# remote_0_1.net
KiCad netlist of a schematic drawn in EAGLE
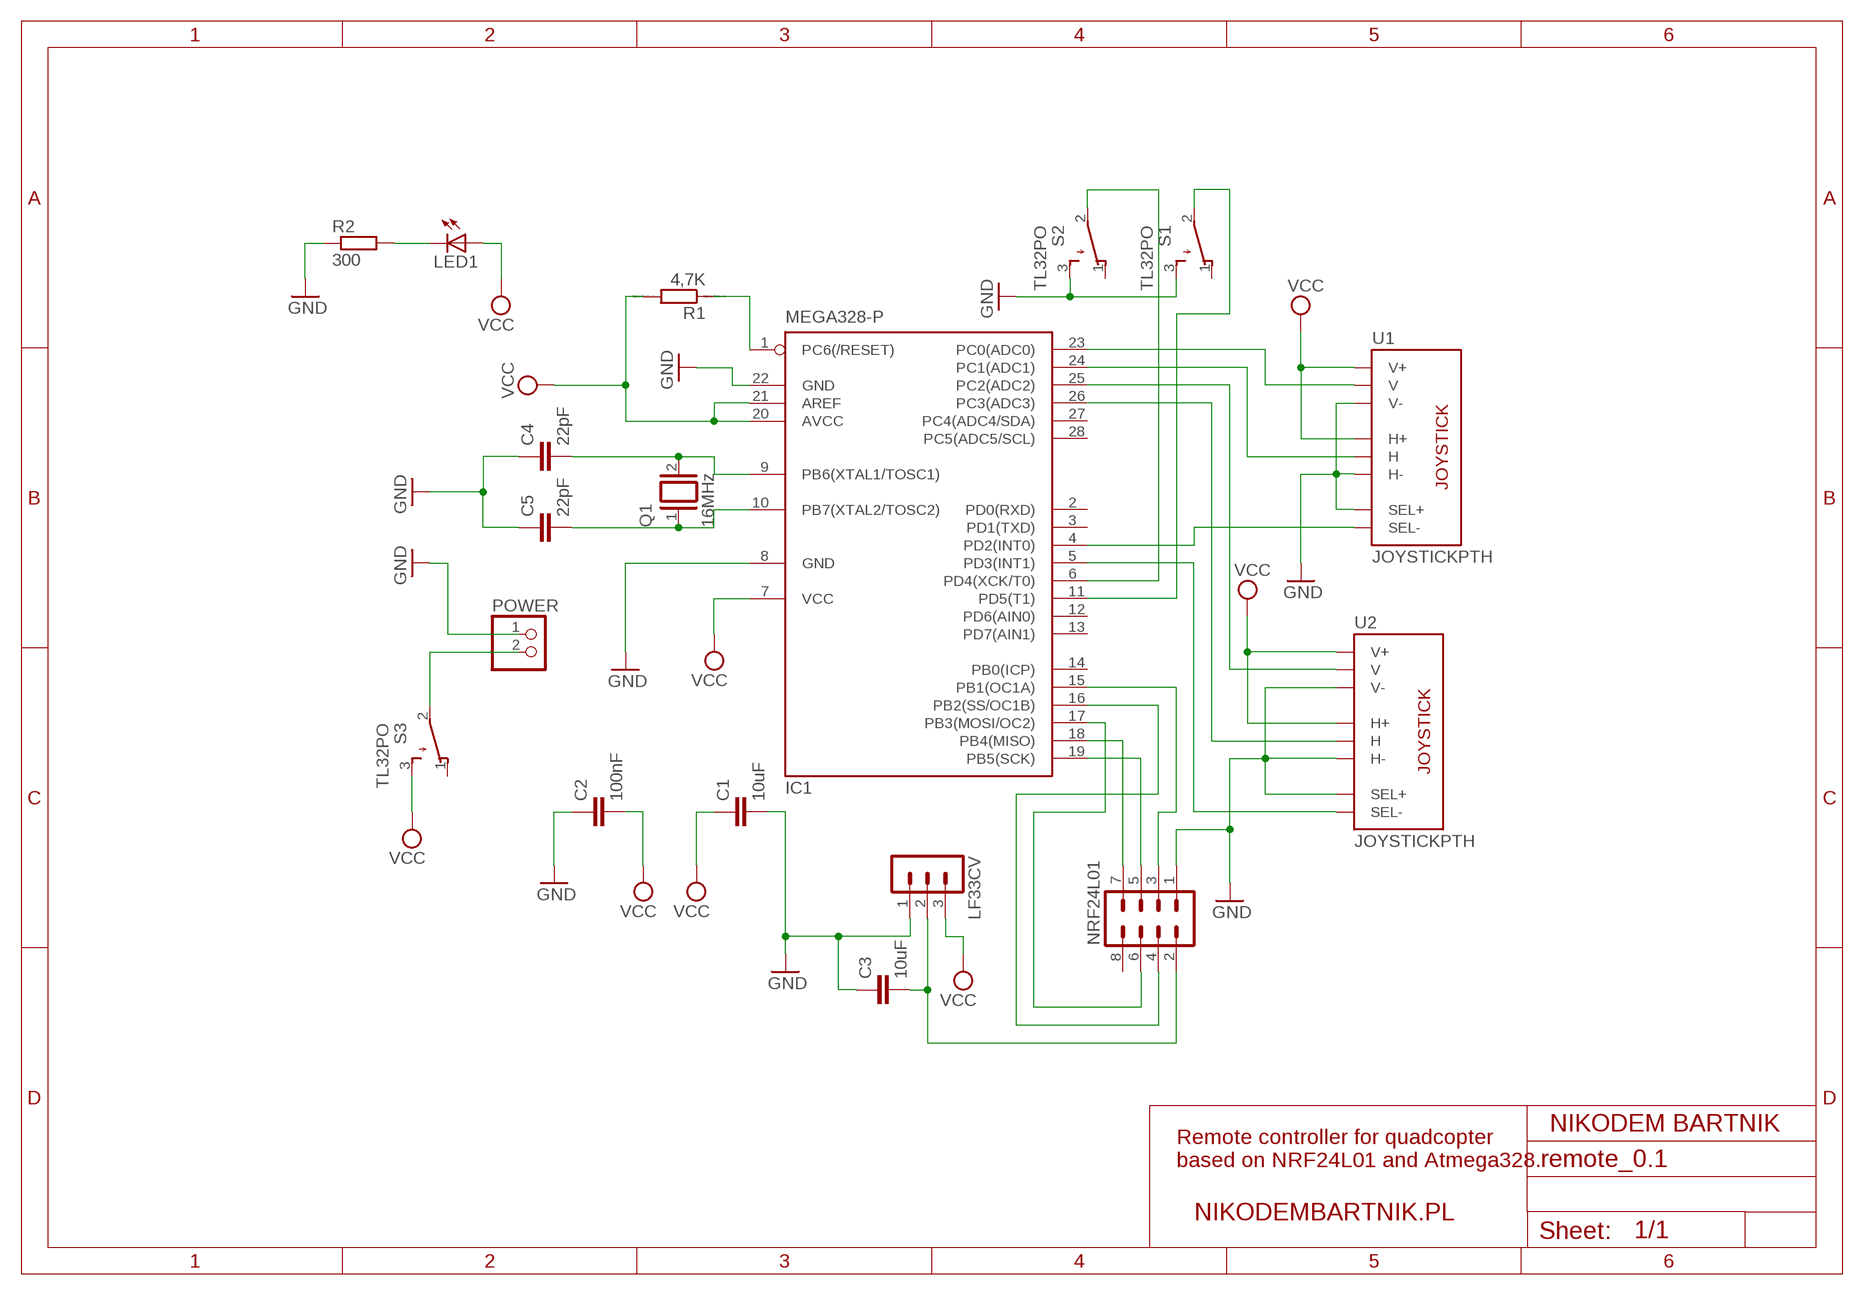
[diagram p0: schematic, sheet 1]

(export (version "E")
  (design (tool "Eeschema 10.0.6"))
  (components
    (comp (ref "C1")
      (value "10uF")
      (footprint "eagle-import:C2.5-3")
      (libsource (lib "eagle-import") (part "C2,5-3"))
    )
    (comp (ref "C2")
      (value "100nF")
      (footprint "eagle-import:C2.5-3")
      (libsource (lib "eagle-import") (part "C2,5-3"))
    )
    (comp (ref "C3")
      (value "10uF")
      (footprint "eagle-import:C2.5-3")
      (libsource (lib "eagle-import") (part "C2,5-3"))
    )
    (comp (ref "C4")
      (value "22pF")
      (footprint "eagle-import:CAP-PTH-SMALL-KIT")
      (libsource (lib "eagle-import") (part "CAPKIT"))
    )
    (comp (ref "C5")
      (value "22pF")
      (footprint "eagle-import:CAP-PTH-SMALL-KIT")
      (libsource (lib "eagle-import") (part "CAPKIT"))
    )
    (comp (ref "IC1")
      (value "MEGA328-P")
      (footprint "eagle-import:DIL28-3")
      (libsource (lib "eagle-import") (part "MEGA8-P"))
    )
    (comp (ref "LED1")
      (value "LED5MM")
      (footprint "eagle-import:LED5MM")
      (libsource (lib "eagle-import") (part "LED5MM"))
    )
    (comp (ref "LF33CV")
      (value "MA03-1")
      (footprint "eagle-import:MA03-1")
      (libsource (lib "eagle-import") (part "MA03-1"))
    )
    (comp (ref "NRF24L01")
      (value "MA04-2")
      (footprint "eagle-import:MA04-2")
      (libsource (lib "eagle-import") (part "MA04-2"))
    )
    (comp (ref "POWER")
      (value "PINHD-1X2")
      (footprint "eagle-import:1X02")
      (libsource (lib "eagle-import") (part "PINHD-1X2"))
    )
    (comp (ref "Q1")
      (value "16MHz")
      (footprint "eagle-import:QS")
      (libsource (lib "eagle-import") (part "XTAL/S"))
    )
    (comp (ref "R1")
      (value "4,7K")
      (footprint "eagle-import:0204_7")
      (libsource (lib "eagle-import") (part "R0204/7"))
    )
    (comp (ref "R2")
      (value "300")
      (footprint "eagle-import:0204_5")
      (libsource (lib "eagle-import") (part "R-EU_0204/5"))
    )
    (comp (ref "S1")
      (value "TL32PO")
      (footprint "eagle-import:TL3XPO")
      (libsource (lib "eagle-import") (part "TL32PO"))
    )
    (comp (ref "S2")
      (value "TL32PO")
      (footprint "eagle-import:TL3XPO")
      (libsource (lib "eagle-import") (part "TL32PO"))
    )
    (comp (ref "S3")
      (value "TL32PO")
      (footprint "eagle-import:TL3XPO")
      (libsource (lib "eagle-import") (part "TL32PO"))
    )
    (comp (ref "U1")
      (value "JOYSTICKPTH")
      (footprint "eagle-import:JOYSTICK")
      (libsource (lib "eagle-import") (part "JOYSTICKPTH"))
    )
    (comp (ref "U2")
      (value "JOYSTICKPTH")
      (footprint "eagle-import:JOYSTICK")
      (libsource (lib "eagle-import") (part "JOYSTICKPTH"))
    )
  )
  (nets
    (net (code "1") (name "GND") (class "Default")
      (node (ref "C1") (pin "2") (pinfunction "2_2") (pintype "passive"))
      (node (ref "C2") (pin "1") (pinfunction "1_1") (pintype "passive"))
      (node (ref "C3") (pin "1") (pinfunction "1_1") (pintype "passive"))
      (node (ref "C4") (pin "1") (pinfunction "1_1") (pintype "passive"))
      (node (ref "C5") (pin "1") (pinfunction "1_1") (pintype "passive"))
      (node (ref "IC1") (pin "22") (pinfunction "GND_22") (pintype "power_in"))
      (node (ref "IC1") (pin "8") (pinfunction "GND_8") (pintype "power_in"))
      (node (ref "LF33CV") (pin "1") (pinfunction "1_1") (pintype "passive"))
      (node (ref "NRF24L01") (pin "1") (pinfunction "1_1") (pintype "passive"))
      (node (ref "POWER") (pin "1") (pinfunction "1_1") (pintype "passive"))
      (node (ref "R2") (pin "1") (pinfunction "1_1") (pintype "passive"))
      (node (ref "S1") (pin "3") (pinfunction "S_3") (pintype "passive"))
      (node (ref "S2") (pin "3") (pinfunction "S_3") (pintype "passive"))
      (node (ref "U1") (pin "B1A") (pinfunction "SEL+_B1A") (pintype "bidirectional"))
      (node (ref "U1") (pin "H3") (pinfunction "H-_H3") (pintype "bidirectional"))
      (node (ref "U1") (pin "V3") (pinfunction "V-_V3") (pintype "bidirectional"))
      (node (ref "U2") (pin "B1A") (pinfunction "SEL+_B1A") (pintype "bidirectional"))
      (node (ref "U2") (pin "H3") (pinfunction "H-_H3") (pintype "bidirectional"))
      (node (ref "U2") (pin "V3") (pinfunction "V-_V3") (pintype "bidirectional"))
    )
    (net (code "2") (name "Net-(C3-Pad2)") (class "Default")
      (node (ref "C3") (pin "2") (pinfunction "2_2") (pintype "passive"))
      (node (ref "LF33CV") (pin "2") (pinfunction "2_2") (pintype "passive"))
      (node (ref "NRF24L01") (pin "2") (pinfunction "2_2") (pintype "passive"))
    )
    (net (code "3") (name "Net-(IC1-PB1(OC1A))") (class "Default")
      (node (ref "IC1") (pin "15") (pinfunction "PB1(OC1A)_15") (pintype "bidirectional"))
      (node (ref "NRF24L01") (pin "3") (pinfunction "3_3") (pintype "passive"))
    )
    (net (code "4") (name "Net-(IC1-PB2(SS{slash}OC1B))") (class "Default")
      (node (ref "IC1") (pin "16") (pinfunction "PB2(SS/OC1B)_16") (pintype "bidirectional"))
      (node (ref "NRF24L01") (pin "4") (pinfunction "4_4") (pintype "passive"))
    )
    (net (code "5") (name "Net-(IC1-PB3(MOSI{slash}OC2))") (class "Default")
      (node (ref "IC1") (pin "17") (pinfunction "PB3(MOSI/OC2)_17") (pintype "bidirectional"))
      (node (ref "NRF24L01") (pin "6") (pinfunction "6_6") (pintype "passive"))
    )
    (net (code "6") (name "Net-(IC1-PB4(MISO))") (class "Default")
      (node (ref "IC1") (pin "18") (pinfunction "PB4(MISO)_18") (pintype "bidirectional"))
      (node (ref "NRF24L01") (pin "7") (pinfunction "7_7") (pintype "passive"))
    )
    (net (code "7") (name "Net-(IC1-PB5(SCK))") (class "Default")
      (node (ref "IC1") (pin "19") (pinfunction "PB5(SCK)_19") (pintype "bidirectional"))
      (node (ref "NRF24L01") (pin "5") (pinfunction "5_5") (pintype "passive"))
    )
    (net (code "8") (name "Net-(IC1-PB6(XTAL1{slash}TOSC1))") (class "Default")
      (node (ref "C4") (pin "2") (pinfunction "2_2") (pintype "passive"))
      (node (ref "IC1") (pin "9") (pinfunction "PB6(XTAL1/TOSC1)_9") (pintype "bidirectional"))
      (node (ref "Q1") (pin "2") (pinfunction "2_2") (pintype "passive"))
    )
    (net (code "9") (name "Net-(IC1-PB7(XTAL2{slash}TOSC2))") (class "Default")
      (node (ref "C5") (pin "2") (pinfunction "2_2") (pintype "passive"))
      (node (ref "IC1") (pin "10") (pinfunction "PB7(XTAL2/TOSC2)_10") (pintype "bidirectional"))
      (node (ref "Q1") (pin "1") (pinfunction "1_1") (pintype "passive"))
    )
    (net (code "10") (name "Net-(IC1-PC0(ADC0))") (class "Default")
      (node (ref "IC1") (pin "23") (pinfunction "PC0(ADC0)_23") (pintype "bidirectional"))
      (node (ref "U1") (pin "V2") (pinfunction "V_V2") (pintype "bidirectional"))
    )
    (net (code "11") (name "Net-(IC1-PC1(ADC1))") (class "Default")
      (node (ref "IC1") (pin "24") (pinfunction "PC1(ADC1)_24") (pintype "bidirectional"))
      (node (ref "U1") (pin "H2") (pinfunction "H_H2") (pintype "bidirectional"))
    )
    (net (code "12") (name "Net-(IC1-PC2(ADC2))") (class "Default")
      (node (ref "IC1") (pin "25") (pinfunction "PC2(ADC2)_25") (pintype "bidirectional"))
      (node (ref "U2") (pin "V2") (pinfunction "V_V2") (pintype "bidirectional"))
    )
    (net (code "13") (name "Net-(IC1-PC3(ADC3))") (class "Default")
      (node (ref "IC1") (pin "26") (pinfunction "PC3(ADC3)_26") (pintype "bidirectional"))
      (node (ref "U2") (pin "H2") (pinfunction "H_H2") (pintype "bidirectional"))
    )
    (net (code "14") (name "Net-(IC1-PC6({slash}RESET))") (class "Default")
      (node (ref "IC1") (pin "1") (pinfunction "PC6(/RESET)_1") (pintype "bidirectional"))
      (node (ref "R1") (pin "1") (pinfunction "1_1") (pintype "passive"))
    )
    (net (code "15") (name "Net-(IC1-PD2(INT0))") (class "Default")
      (node (ref "IC1") (pin "4") (pinfunction "PD2(INT0)_4") (pintype "bidirectional"))
      (node (ref "U1") (pin "B2A") (pinfunction "SEL-_B2A") (pintype "bidirectional"))
    )
    (net (code "16") (name "Net-(IC1-PD3(INT1))") (class "Default")
      (node (ref "IC1") (pin "5") (pinfunction "PD3(INT1)_5") (pintype "bidirectional"))
      (node (ref "U2") (pin "B2A") (pinfunction "SEL-_B2A") (pintype "bidirectional"))
    )
    (net (code "17") (name "Net-(IC1-PD4(XCK{slash}T0))") (class "Default")
      (node (ref "IC1") (pin "6") (pinfunction "PD4(XCK/T0)_6") (pintype "bidirectional"))
      (node (ref "S2") (pin "2") (pinfunction "P_2") (pintype "passive"))
    )
    (net (code "18") (name "Net-(IC1-PD5(T1))") (class "Default")
      (node (ref "IC1") (pin "11") (pinfunction "PD5(T1)_11") (pintype "bidirectional"))
      (node (ref "S1") (pin "2") (pinfunction "P_2") (pintype "passive"))
    )
    (net (code "19") (name "Net-(LED1-C)") (class "Default")
      (node (ref "LED1") (pin "K") (pinfunction "C_K") (pintype "passive"))
      (node (ref "R2") (pin "2") (pinfunction "2_2") (pintype "passive"))
    )
    (net (code "20") (name "Net-(S3-P)") (class "Default")
      (node (ref "POWER") (pin "2") (pinfunction "2_2") (pintype "passive"))
      (node (ref "S3") (pin "2") (pinfunction "P_2") (pintype "passive"))
    )
    (net (code "21") (name "VCC") (class "Default")
      (node (ref "C1") (pin "1") (pinfunction "1_1") (pintype "passive"))
      (node (ref "C2") (pin "2") (pinfunction "2_2") (pintype "passive"))
      (node (ref "IC1") (pin "20") (pinfunction "AVCC_20") (pintype "power_in"))
      (node (ref "IC1") (pin "21") (pinfunction "AREF_21") (pintype "passive"))
      (node (ref "IC1") (pin "7") (pinfunction "VCC_7") (pintype "power_in"))
      (node (ref "LED1") (pin "A") (pinfunction "A_A") (pintype "passive"))
      (node (ref "LF33CV") (pin "3") (pinfunction "3_3") (pintype "passive"))
      (node (ref "R1") (pin "2") (pinfunction "2_2") (pintype "passive"))
      (node (ref "S3") (pin "3") (pinfunction "S_3") (pintype "passive"))
      (node (ref "U1") (pin "H1") (pinfunction "H+_H1") (pintype "bidirectional"))
      (node (ref "U1") (pin "V1") (pinfunction "V+_V1") (pintype "bidirectional"))
      (node (ref "U2") (pin "H1") (pinfunction "H+_H1") (pintype "bidirectional"))
      (node (ref "U2") (pin "V1") (pinfunction "V+_V1") (pintype "bidirectional"))
    )
    (net (code "22") (name "unconnected-(IC1-PB0(ICP)-Pad14)") (class "Default")
      (node (ref "IC1") (pin "14") (pinfunction "PB0(ICP)_14") (pintype "bidirectional"))
    )
    (net (code "23") (name "unconnected-(IC1-PC4(ADC4{slash}SDA)-Pad27)") (class "Default")
      (node (ref "IC1") (pin "27") (pinfunction "PC4(ADC4/SDA)_27") (pintype "bidirectional"))
    )
    (net (code "24") (name "unconnected-(IC1-PC5(ADC5{slash}SCL)-Pad28)") (class "Default")
      (node (ref "IC1") (pin "28") (pinfunction "PC5(ADC5/SCL)_28") (pintype "bidirectional"))
    )
    (net (code "25") (name "unconnected-(IC1-PD0(RXD)-Pad2)") (class "Default")
      (node (ref "IC1") (pin "2") (pinfunction "PD0(RXD)_2") (pintype "bidirectional"))
    )
    (net (code "26") (name "unconnected-(IC1-PD1(TXD)-Pad3)") (class "Default")
      (node (ref "IC1") (pin "3") (pinfunction "PD1(TXD)_3") (pintype "bidirectional"))
    )
    (net (code "27") (name "unconnected-(IC1-PD6(AIN0)-Pad12)") (class "Default")
      (node (ref "IC1") (pin "12") (pinfunction "PD6(AIN0)_12") (pintype "bidirectional"))
    )
    (net (code "28") (name "unconnected-(IC1-PD7(AIN1)-Pad13)") (class "Default")
      (node (ref "IC1") (pin "13") (pinfunction "PD7(AIN1)_13") (pintype "bidirectional"))
    )
    (net (code "29") (name "unconnected-(NRF24L01-Pad8)") (class "Default")
      (node (ref "NRF24L01") (pin "8") (pinfunction "8_8") (pintype "passive"))
    )
    (net (code "30") (name "unconnected-(S1-O-Pad1)") (class "Default")
      (node (ref "S1") (pin "1") (pinfunction "O_1") (pintype "passive"))
    )
    (net (code "31") (name "unconnected-(S2-O-Pad1)") (class "Default")
      (node (ref "S2") (pin "1") (pinfunction "O_1") (pintype "passive"))
    )
    (net (code "32") (name "unconnected-(S3-O-Pad1)") (class "Default")
      (node (ref "S3") (pin "1") (pinfunction "O_1") (pintype "passive"))
    )
  )
)
